# CAL_logics.net
KiCad netlist of a schematic drawn in Altium Designer
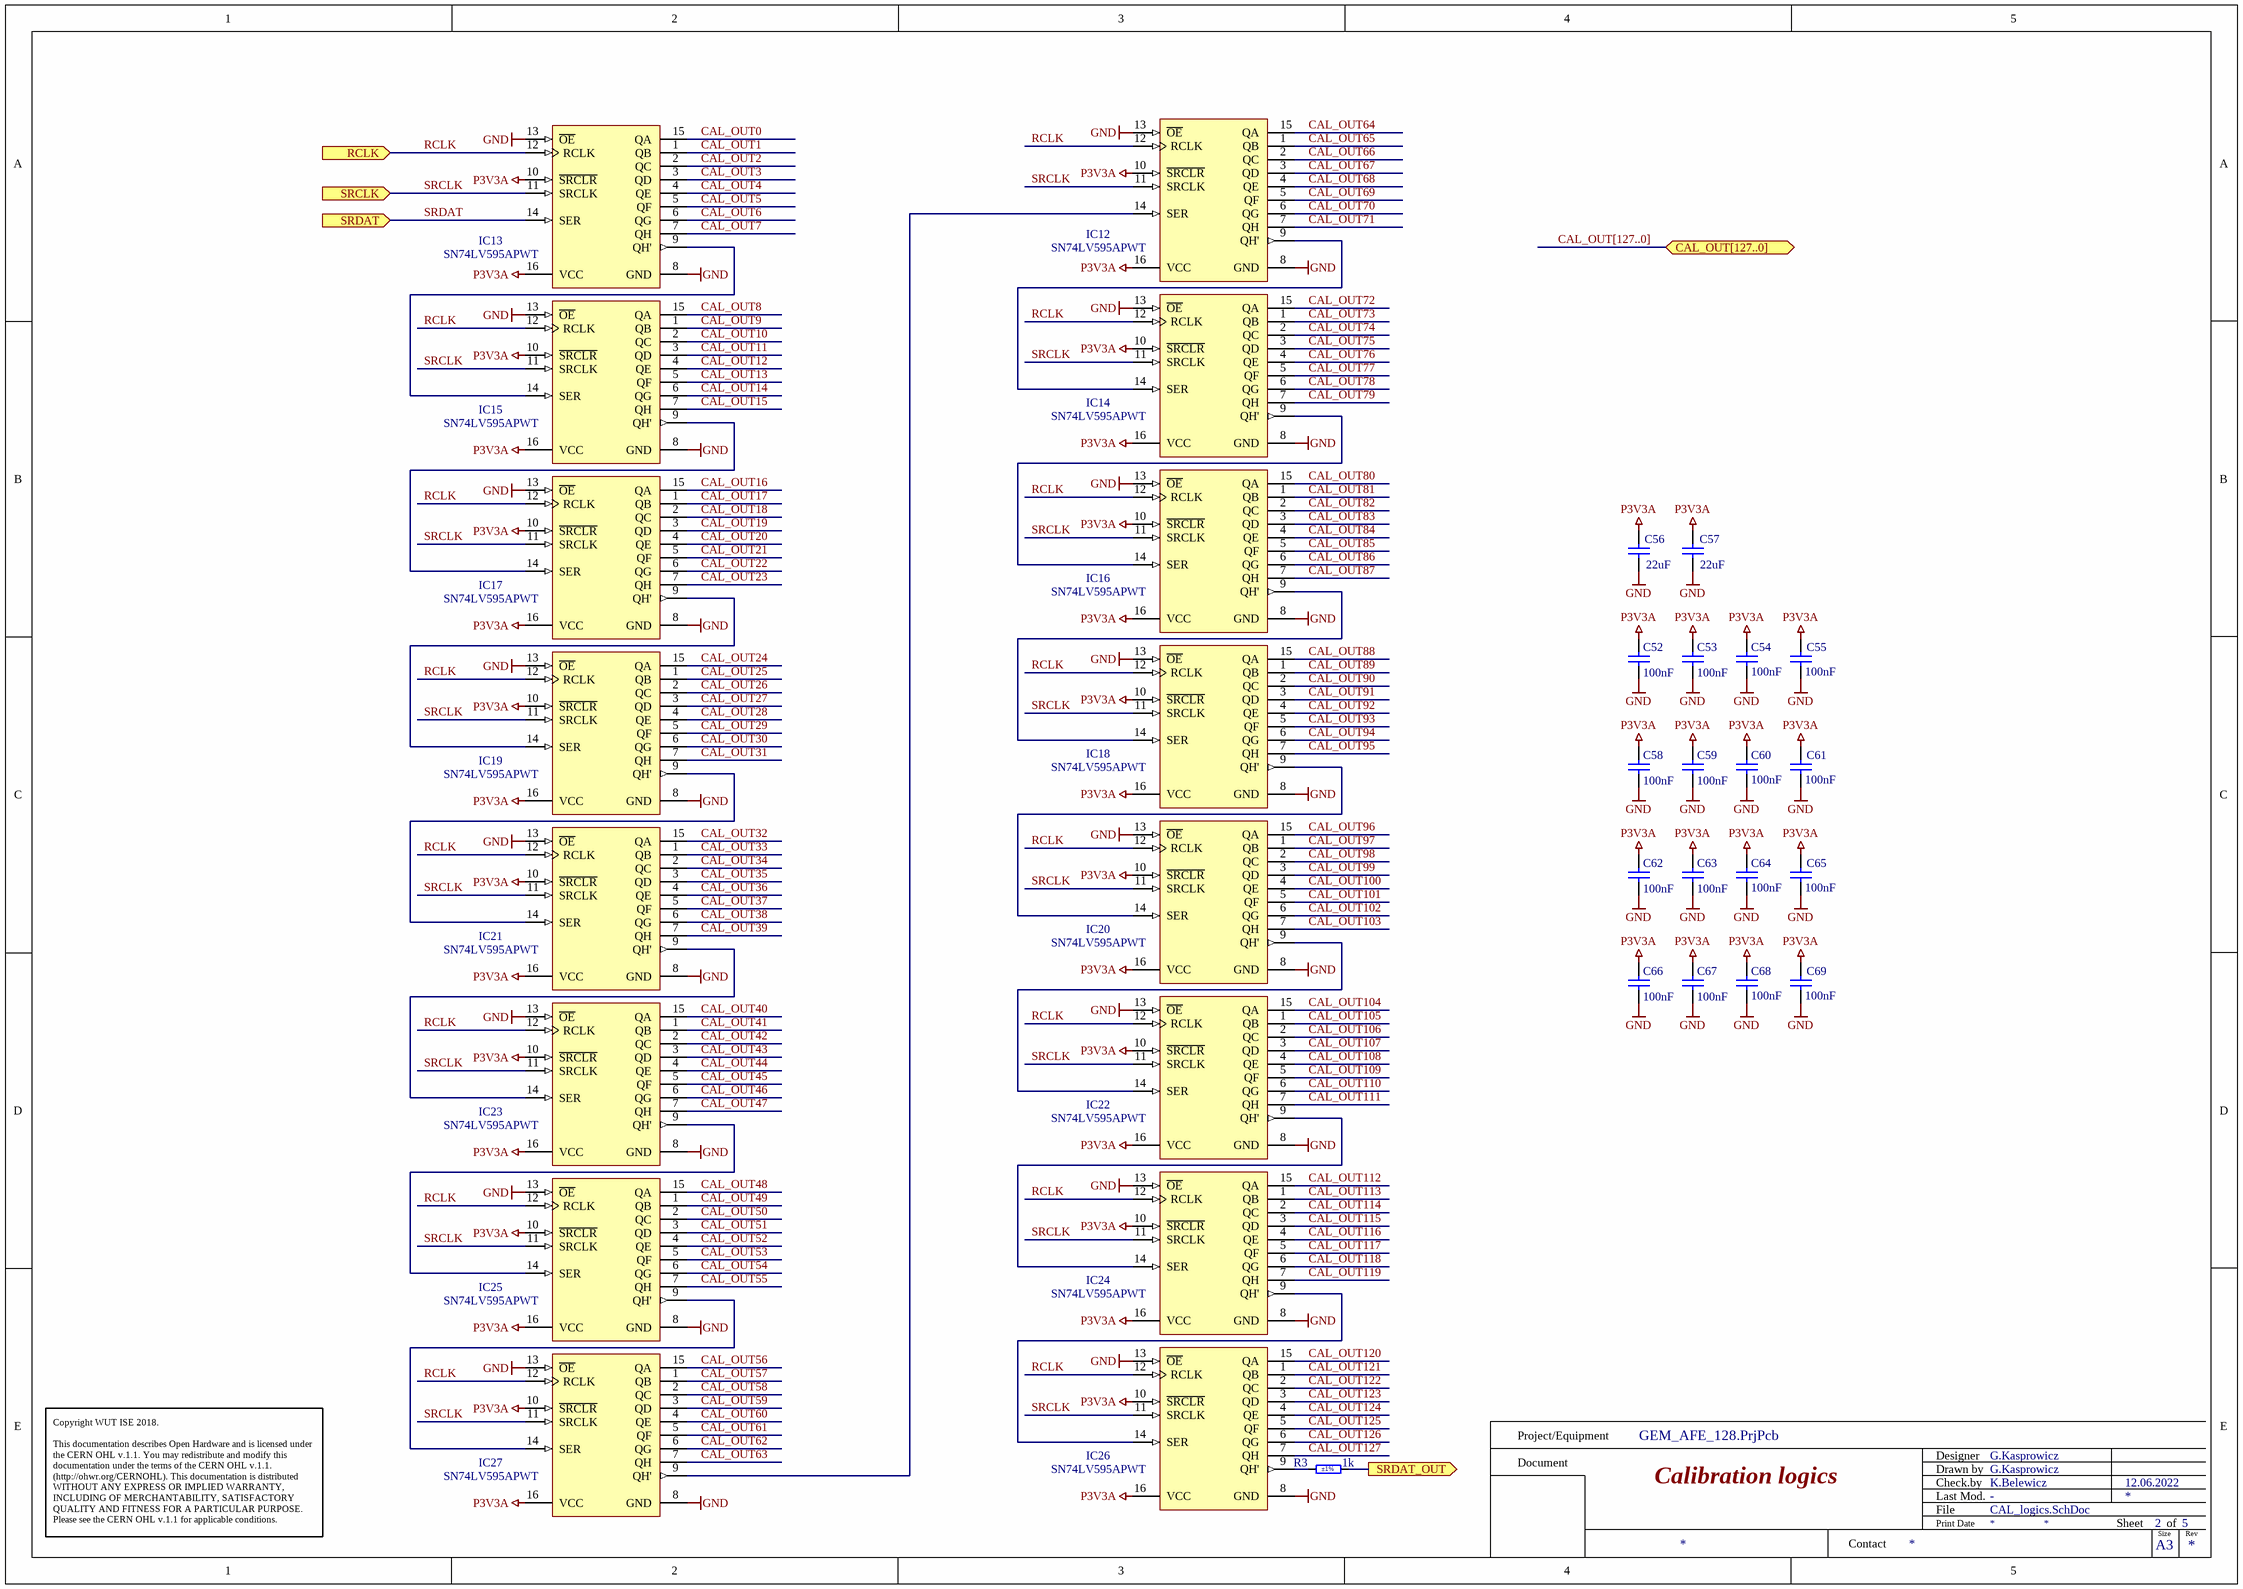
[diagram p0: CAL_logics.SchDoc]

(export (version "E")
  (design (tool "Eeschema 10.0.6"))
  (components
    (comp (ref "C52")
      (value "100nF")
      (footprint "CAPC1005X55N")
      (description "Non-polarised capacitor")
      (fields
        (field (name "PART NUMBER") "CC0402_100NF_16V_10%_X7R")
        (field (name "VOLTAGE") "16V")
        (field (name "AUTHOR") "CERN DEM JLC")
      )
      (libsource (lib "Capacitors") (part "Capacitor - non polarized"))
    )
    (comp (ref "C53")
      (value "100nF")
      (footprint "CAPC1005X55N")
      (description "Non-polarised capacitor")
      (fields
        (field (name "PART NUMBER") "CC0402_100NF_16V_10%_X7R")
        (field (name "VOLTAGE") "16V")
        (field (name "AUTHOR") "CERN DEM JLC")
      )
      (libsource (lib "Capacitors") (part "Capacitor - non polarized"))
    )
    (comp (ref "C54")
      (value "100nF")
      (footprint "CAPC1005X55N")
      (description "Non-polarised capacitor")
      (fields
        (field (name "PART NUMBER") "CC0402_100NF_16V_10%_X7R")
        (field (name "VOLTAGE") "16V")
        (field (name "AUTHOR") "CERN DEM JLC")
      )
      (libsource (lib "Capacitors") (part "Capacitor - non polarized"))
    )
    (comp (ref "C55")
      (value "100nF")
      (footprint "CAPC1005X55N")
      (description "Non-polarised capacitor")
      (fields
        (field (name "PART NUMBER") "CC0402_100NF_16V_10%_X7R")
        (field (name "VOLTAGE") "16V")
        (field (name "AUTHOR") "CERN DEM JLC")
      )
      (libsource (lib "Capacitors") (part "Capacitor - non polarized"))
    )
    (comp (ref "C56")
      (value "22uF")
      (footprint "CAPC3216X140N")
      (description "Non-polarised capacitor")
      (fields
        (field (name "PART NUMBER") "CC1206_22UF_6.3V_20%_X5R")
        (field (name "VOLTAGE") "6.3V")
        (field (name "AUTHOR") "CERN DEM JLC")
      )
      (libsource (lib "Capacitors") (part "Capacitor - non polarized"))
    )
    (comp (ref "C57")
      (value "22uF")
      (footprint "CAPC3216X140N")
      (description "Non-polarised capacitor")
      (fields
        (field (name "PART NUMBER") "CC1206_22UF_6.3V_20%_X5R")
        (field (name "VOLTAGE") "6.3V")
        (field (name "AUTHOR") "CERN DEM JLC")
      )
      (libsource (lib "Capacitors") (part "Capacitor - non polarized"))
    )
    (comp (ref "C58")
      (value "100nF")
      (footprint "CAPC1005X55N")
      (description "Non-polarised capacitor")
      (fields
        (field (name "PART NUMBER") "CC0402_100NF_16V_10%_X7R")
        (field (name "VOLTAGE") "16V")
        (field (name "AUTHOR") "CERN DEM JLC")
      )
      (libsource (lib "Capacitors") (part "Capacitor - non polarized"))
    )
    (comp (ref "C59")
      (value "100nF")
      (footprint "CAPC1005X55N")
      (description "Non-polarised capacitor")
      (fields
        (field (name "PART NUMBER") "CC0402_100NF_16V_10%_X7R")
        (field (name "VOLTAGE") "16V")
        (field (name "AUTHOR") "CERN DEM JLC")
      )
      (libsource (lib "Capacitors") (part "Capacitor - non polarized"))
    )
    (comp (ref "C60")
      (value "100nF")
      (footprint "CAPC1005X55N")
      (description "Non-polarised capacitor")
      (fields
        (field (name "PART NUMBER") "CC0402_100NF_16V_10%_X7R")
        (field (name "VOLTAGE") "16V")
        (field (name "AUTHOR") "CERN DEM JLC")
      )
      (libsource (lib "Capacitors") (part "Capacitor - non polarized"))
    )
    (comp (ref "C61")
      (value "100nF")
      (footprint "CAPC1005X55N")
      (description "Non-polarised capacitor")
      (fields
        (field (name "PART NUMBER") "CC0402_100NF_16V_10%_X7R")
        (field (name "VOLTAGE") "16V")
        (field (name "AUTHOR") "CERN DEM JLC")
      )
      (libsource (lib "Capacitors") (part "Capacitor - non polarized"))
    )
    (comp (ref "C62")
      (value "100nF")
      (footprint "CAPC1005X55N")
      (description "Non-polarised capacitor")
      (fields
        (field (name "PART NUMBER") "CC0402_100NF_16V_10%_X7R")
        (field (name "VOLTAGE") "16V")
        (field (name "AUTHOR") "CERN DEM JLC")
      )
      (libsource (lib "Capacitors") (part "Capacitor - non polarized"))
    )
    (comp (ref "C63")
      (value "100nF")
      (footprint "CAPC1005X55N")
      (description "Non-polarised capacitor")
      (fields
        (field (name "PART NUMBER") "CC0402_100NF_16V_10%_X7R")
        (field (name "VOLTAGE") "16V")
        (field (name "AUTHOR") "CERN DEM JLC")
      )
      (libsource (lib "Capacitors") (part "Capacitor - non polarized"))
    )
    (comp (ref "C64")
      (value "100nF")
      (footprint "CAPC1005X55N")
      (description "Non-polarised capacitor")
      (fields
        (field (name "PART NUMBER") "CC0402_100NF_16V_10%_X7R")
        (field (name "VOLTAGE") "16V")
        (field (name "AUTHOR") "CERN DEM JLC")
      )
      (libsource (lib "Capacitors") (part "Capacitor - non polarized"))
    )
    (comp (ref "C65")
      (value "100nF")
      (footprint "CAPC1005X55N")
      (description "Non-polarised capacitor")
      (fields
        (field (name "PART NUMBER") "CC0402_100NF_16V_10%_X7R")
        (field (name "VOLTAGE") "16V")
        (field (name "AUTHOR") "CERN DEM JLC")
      )
      (libsource (lib "Capacitors") (part "Capacitor - non polarized"))
    )
    (comp (ref "C66")
      (value "100nF")
      (footprint "CAPC1005X55N")
      (description "Non-polarised capacitor")
      (fields
        (field (name "PART NUMBER") "CC0402_100NF_16V_10%_X7R")
        (field (name "VOLTAGE") "16V")
        (field (name "AUTHOR") "CERN DEM JLC")
      )
      (libsource (lib "Capacitors") (part "Capacitor - non polarized"))
    )
    (comp (ref "C67")
      (value "100nF")
      (footprint "CAPC1005X55N")
      (description "Non-polarised capacitor")
      (fields
        (field (name "PART NUMBER") "CC0402_100NF_16V_10%_X7R")
        (field (name "VOLTAGE") "16V")
        (field (name "AUTHOR") "CERN DEM JLC")
      )
      (libsource (lib "Capacitors") (part "Capacitor - non polarized"))
    )
    (comp (ref "C68")
      (value "100nF")
      (footprint "CAPC1005X55N")
      (description "Non-polarised capacitor")
      (fields
        (field (name "PART NUMBER") "CC0402_100NF_16V_10%_X7R")
        (field (name "VOLTAGE") "16V")
        (field (name "AUTHOR") "CERN DEM JLC")
      )
      (libsource (lib "Capacitors") (part "Capacitor - non polarized"))
    )
    (comp (ref "C69")
      (value "100nF")
      (footprint "CAPC1005X55N")
      (description "Non-polarised capacitor")
      (fields
        (field (name "PART NUMBER") "CC0402_100NF_16V_10%_X7R")
        (field (name "VOLTAGE") "16V")
        (field (name "AUTHOR") "CERN DEM JLC")
      )
      (libsource (lib "Capacitors") (part "Capacitor - non polarized"))
    )
    (comp (ref "IC12")
      (value "SN74LV595APWT")
      (footprint "SOP65P640X120-16N")
      (description "8-Bit Shift Register With 3-State Output Register")
      (fields (field (name "MANUFACTURER") "TEXAS INSTRUMENTS") (field (name "AUTHOR") "CERN DEM JLC"))
      (libsource (lib "ICs And Semiconductors") (part "74595"))
    )
    (comp (ref "IC13")
      (value "SN74LV595APWT")
      (footprint "SOP65P640X120-16N")
      (description "8-Bit Shift Register With 3-State Output Register")
      (fields (field (name "MANUFACTURER") "TEXAS INSTRUMENTS") (field (name "AUTHOR") "CERN DEM JLC"))
      (libsource (lib "ICs And Semiconductors") (part "74595"))
    )
    (comp (ref "IC14")
      (value "SN74LV595APWT")
      (footprint "SOP65P640X120-16N")
      (description "8-Bit Shift Register With 3-State Output Register")
      (fields (field (name "MANUFACTURER") "TEXAS INSTRUMENTS") (field (name "AUTHOR") "CERN DEM JLC"))
      (libsource (lib "ICs And Semiconductors") (part "74595"))
    )
    (comp (ref "IC15")
      (value "SN74LV595APWT")
      (footprint "SOP65P640X120-16N")
      (description "8-Bit Shift Register With 3-State Output Register")
      (fields (field (name "MANUFACTURER") "TEXAS INSTRUMENTS") (field (name "AUTHOR") "CERN DEM JLC"))
      (libsource (lib "ICs And Semiconductors") (part "74595"))
    )
    (comp (ref "IC16")
      (value "SN74LV595APWT")
      (footprint "SOP65P640X120-16N")
      (description "8-Bit Shift Register With 3-State Output Register")
      (fields (field (name "MANUFACTURER") "TEXAS INSTRUMENTS") (field (name "AUTHOR") "CERN DEM JLC"))
      (libsource (lib "ICs And Semiconductors") (part "74595"))
    )
    (comp (ref "IC17")
      (value "SN74LV595APWT")
      (footprint "SOP65P640X120-16N")
      (description "8-Bit Shift Register With 3-State Output Register")
      (fields (field (name "MANUFACTURER") "TEXAS INSTRUMENTS") (field (name "AUTHOR") "CERN DEM JLC"))
      (libsource (lib "ICs And Semiconductors") (part "74595"))
    )
    (comp (ref "IC18")
      (value "SN74LV595APWT")
      (footprint "SOP65P640X120-16N")
      (description "8-Bit Shift Register With 3-State Output Register")
      (fields (field (name "MANUFACTURER") "TEXAS INSTRUMENTS") (field (name "AUTHOR") "CERN DEM JLC"))
      (libsource (lib "ICs And Semiconductors") (part "74595"))
    )
    (comp (ref "IC19")
      (value "SN74LV595APWT")
      (footprint "SOP65P640X120-16N")
      (description "8-Bit Shift Register With 3-State Output Register")
      (fields (field (name "MANUFACTURER") "TEXAS INSTRUMENTS") (field (name "AUTHOR") "CERN DEM JLC"))
      (libsource (lib "ICs And Semiconductors") (part "74595"))
    )
    (comp (ref "IC20")
      (value "SN74LV595APWT")
      (footprint "SOP65P640X120-16N")
      (description "8-Bit Shift Register With 3-State Output Register")
      (fields (field (name "MANUFACTURER") "TEXAS INSTRUMENTS") (field (name "AUTHOR") "CERN DEM JLC"))
      (libsource (lib "ICs And Semiconductors") (part "74595"))
    )
    (comp (ref "IC21")
      (value "SN74LV595APWT")
      (footprint "SOP65P640X120-16N")
      (description "8-Bit Shift Register With 3-State Output Register")
      (fields (field (name "MANUFACTURER") "TEXAS INSTRUMENTS") (field (name "AUTHOR") "CERN DEM JLC"))
      (libsource (lib "ICs And Semiconductors") (part "74595"))
    )
    (comp (ref "IC22")
      (value "SN74LV595APWT")
      (footprint "SOP65P640X120-16N")
      (description "8-Bit Shift Register With 3-State Output Register")
      (fields (field (name "MANUFACTURER") "TEXAS INSTRUMENTS") (field (name "AUTHOR") "CERN DEM JLC"))
      (libsource (lib "ICs And Semiconductors") (part "74595"))
    )
    (comp (ref "IC23")
      (value "SN74LV595APWT")
      (footprint "SOP65P640X120-16N")
      (description "8-Bit Shift Register With 3-State Output Register")
      (fields (field (name "MANUFACTURER") "TEXAS INSTRUMENTS") (field (name "AUTHOR") "CERN DEM JLC"))
      (libsource (lib "ICs And Semiconductors") (part "74595"))
    )
    (comp (ref "IC24")
      (value "SN74LV595APWT")
      (footprint "SOP65P640X120-16N")
      (description "8-Bit Shift Register With 3-State Output Register")
      (fields (field (name "MANUFACTURER") "TEXAS INSTRUMENTS") (field (name "AUTHOR") "CERN DEM JLC"))
      (libsource (lib "ICs And Semiconductors") (part "74595"))
    )
    (comp (ref "IC25")
      (value "SN74LV595APWT")
      (footprint "SOP65P640X120-16N")
      (description "8-Bit Shift Register With 3-State Output Register")
      (fields (field (name "MANUFACTURER") "TEXAS INSTRUMENTS") (field (name "AUTHOR") "CERN DEM JLC"))
      (libsource (lib "ICs And Semiconductors") (part "74595"))
    )
    (comp (ref "IC26")
      (value "SN74LV595APWT")
      (footprint "SOP65P640X120-16N")
      (description "8-Bit Shift Register With 3-State Output Register")
      (fields (field (name "MANUFACTURER") "TEXAS INSTRUMENTS") (field (name "AUTHOR") "CERN DEM JLC"))
      (libsource (lib "ICs And Semiconductors") (part "74595"))
    )
    (comp (ref "IC27")
      (value "SN74LV595APWT")
      (footprint "SOP65P640X120-16N")
      (description "8-Bit Shift Register With 3-State Output Register")
      (fields (field (name "MANUFACTURER") "TEXAS INSTRUMENTS") (field (name "AUTHOR") "CERN DEM JLC"))
      (libsource (lib "ICs And Semiconductors") (part "74595"))
    )
    (comp (ref "R3")
      (value "1k")
      (footprint "RESC1005X40N")
      (description "Resistor - 1%")
      (fields
        (field (name "TOLERANCE") "±1%")
        (field (name "PART NUMBER") "R0402_1K_1%_0.0625W_100PPM")
        (field (name "POWER") "0.0625W")
        (field (name "AUTHOR") "CERN DEM JLC")
      )
      (libsource (lib "Resistors") (part "Resistor - 1%"))
    )
  )
  (nets
    (net (code "1") (name "/CAL_OUT0") (class "Default")
      (node (ref "IC13") (pin "15") (pinfunction "QA_15") (pintype "tri_state"))
    )
    (net (code "2") (name "/CAL_OUT1") (class "Default")
      (node (ref "IC13") (pin "1") (pinfunction "QB_1") (pintype "tri_state"))
    )
    (net (code "3") (name "/CAL_OUT2") (class "Default")
      (node (ref "IC13") (pin "2") (pinfunction "QC_2") (pintype "tri_state"))
    )
    (net (code "4") (name "/CAL_OUT3") (class "Default")
      (node (ref "IC13") (pin "3") (pinfunction "QD_3") (pintype "tri_state"))
    )
    (net (code "5") (name "/CAL_OUT4") (class "Default")
      (node (ref "IC13") (pin "4") (pinfunction "QE_4") (pintype "tri_state"))
    )
    (net (code "6") (name "/CAL_OUT5") (class "Default")
      (node (ref "IC13") (pin "5") (pinfunction "QF_5") (pintype "tri_state"))
    )
    (net (code "7") (name "/CAL_OUT6") (class "Default")
      (node (ref "IC13") (pin "6") (pinfunction "QG_6") (pintype "tri_state"))
    )
    (net (code "8") (name "/CAL_OUT7") (class "Default")
      (node (ref "IC13") (pin "7") (pinfunction "QH_7") (pintype "tri_state"))
    )
    (net (code "9") (name "/CAL_OUT8") (class "Default")
      (node (ref "IC15") (pin "15") (pinfunction "QA_15") (pintype "tri_state"))
    )
    (net (code "10") (name "/CAL_OUT9") (class "Default")
      (node (ref "IC15") (pin "1") (pinfunction "QB_1") (pintype "tri_state"))
    )
    (net (code "11") (name "/CAL_OUT10") (class "Default")
      (node (ref "IC15") (pin "2") (pinfunction "QC_2") (pintype "tri_state"))
    )
    (net (code "12") (name "/CAL_OUT11") (class "Default")
      (node (ref "IC15") (pin "3") (pinfunction "QD_3") (pintype "tri_state"))
    )
    (net (code "13") (name "/CAL_OUT12") (class "Default")
      (node (ref "IC15") (pin "4") (pinfunction "QE_4") (pintype "tri_state"))
    )
    (net (code "14") (name "/CAL_OUT13") (class "Default")
      (node (ref "IC15") (pin "5") (pinfunction "QF_5") (pintype "tri_state"))
    )
    (net (code "15") (name "/CAL_OUT14") (class "Default")
      (node (ref "IC15") (pin "6") (pinfunction "QG_6") (pintype "tri_state"))
    )
    (net (code "16") (name "/CAL_OUT15") (class "Default")
      (node (ref "IC15") (pin "7") (pinfunction "QH_7") (pintype "tri_state"))
    )
    (net (code "17") (name "/CAL_OUT16") (class "Default")
      (node (ref "IC17") (pin "15") (pinfunction "QA_15") (pintype "tri_state"))
    )
    (net (code "18") (name "/CAL_OUT17") (class "Default")
      (node (ref "IC17") (pin "1") (pinfunction "QB_1") (pintype "tri_state"))
    )
    (net (code "19") (name "/CAL_OUT18") (class "Default")
      (node (ref "IC17") (pin "2") (pinfunction "QC_2") (pintype "tri_state"))
    )
    (net (code "20") (name "/CAL_OUT19") (class "Default")
      (node (ref "IC17") (pin "3") (pinfunction "QD_3") (pintype "tri_state"))
    )
    (net (code "21") (name "/CAL_OUT20") (class "Default")
      (node (ref "IC17") (pin "4") (pinfunction "QE_4") (pintype "tri_state"))
    )
    (net (code "22") (name "/CAL_OUT21") (class "Default")
      (node (ref "IC17") (pin "5") (pinfunction "QF_5") (pintype "tri_state"))
    )
    (net (code "23") (name "/CAL_OUT22") (class "Default")
      (node (ref "IC17") (pin "6") (pinfunction "QG_6") (pintype "tri_state"))
    )
    (net (code "24") (name "/CAL_OUT23") (class "Default")
      (node (ref "IC17") (pin "7") (pinfunction "QH_7") (pintype "tri_state"))
    )
    (net (code "25") (name "/CAL_OUT24") (class "Default")
      (node (ref "IC19") (pin "15") (pinfunction "QA_15") (pintype "tri_state"))
    )
    (net (code "26") (name "/CAL_OUT25") (class "Default")
      (node (ref "IC19") (pin "1") (pinfunction "QB_1") (pintype "tri_state"))
    )
    (net (code "27") (name "/CAL_OUT26") (class "Default")
      (node (ref "IC19") (pin "2") (pinfunction "QC_2") (pintype "tri_state"))
    )
    (net (code "28") (name "/CAL_OUT27") (class "Default")
      (node (ref "IC19") (pin "3") (pinfunction "QD_3") (pintype "tri_state"))
    )
    (net (code "29") (name "/CAL_OUT28") (class "Default")
      (node (ref "IC19") (pin "4") (pinfunction "QE_4") (pintype "tri_state"))
    )
    (net (code "30") (name "/CAL_OUT29") (class "Default")
      (node (ref "IC19") (pin "5") (pinfunction "QF_5") (pintype "tri_state"))
    )
    (net (code "31") (name "/CAL_OUT30") (class "Default")
      (node (ref "IC19") (pin "6") (pinfunction "QG_6") (pintype "tri_state"))
    )
    (net (code "32") (name "/CAL_OUT31") (class "Default")
      (node (ref "IC19") (pin "7") (pinfunction "QH_7") (pintype "tri_state"))
    )
    (net (code "33") (name "/CAL_OUT32") (class "Default")
      (node (ref "IC21") (pin "15") (pinfunction "QA_15") (pintype "tri_state"))
    )
    (net (code "34") (name "/CAL_OUT33") (class "Default")
      (node (ref "IC21") (pin "1") (pinfunction "QB_1") (pintype "tri_state"))
    )
    (net (code "35") (name "/CAL_OUT34") (class "Default")
      (node (ref "IC21") (pin "2") (pinfunction "QC_2") (pintype "tri_state"))
    )
    (net (code "36") (name "/CAL_OUT35") (class "Default")
      (node (ref "IC21") (pin "3") (pinfunction "QD_3") (pintype "tri_state"))
    )
    (net (code "37") (name "/CAL_OUT36") (class "Default")
      (node (ref "IC21") (pin "4") (pinfunction "QE_4") (pintype "tri_state"))
    )
    (net (code "38") (name "/CAL_OUT37") (class "Default")
      (node (ref "IC21") (pin "5") (pinfunction "QF_5") (pintype "tri_state"))
    )
    (net (code "39") (name "/CAL_OUT38") (class "Default")
      (node (ref "IC21") (pin "6") (pinfunction "QG_6") (pintype "tri_state"))
    )
    (net (code "40") (name "/CAL_OUT39") (class "Default")
      (node (ref "IC21") (pin "7") (pinfunction "QH_7") (pintype "tri_state"))
    )
    (net (code "41") (name "/CAL_OUT40") (class "Default")
      (node (ref "IC23") (pin "15") (pinfunction "QA_15") (pintype "tri_state"))
    )
    (net (code "42") (name "/CAL_OUT41") (class "Default")
      (node (ref "IC23") (pin "1") (pinfunction "QB_1") (pintype "tri_state"))
    )
    (net (code "43") (name "/CAL_OUT42") (class "Default")
      (node (ref "IC23") (pin "2") (pinfunction "QC_2") (pintype "tri_state"))
    )
    (net (code "44") (name "/CAL_OUT43") (class "Default")
      (node (ref "IC23") (pin "3") (pinfunction "QD_3") (pintype "tri_state"))
    )
    (net (code "45") (name "/CAL_OUT44") (class "Default")
      (node (ref "IC23") (pin "4") (pinfunction "QE_4") (pintype "tri_state"))
    )
    (net (code "46") (name "/CAL_OUT45") (class "Default")
      (node (ref "IC23") (pin "5") (pinfunction "QF_5") (pintype "tri_state"))
    )
    (net (code "47") (name "/CAL_OUT46") (class "Default")
      (node (ref "IC23") (pin "6") (pinfunction "QG_6") (pintype "tri_state"))
    )
    (net (code "48") (name "/CAL_OUT47") (class "Default")
      (node (ref "IC23") (pin "7") (pinfunction "QH_7") (pintype "tri_state"))
    )
    (net (code "49") (name "/CAL_OUT48") (class "Default")
      (node (ref "IC25") (pin "15") (pinfunction "QA_15") (pintype "tri_state"))
    )
    (net (code "50") (name "/CAL_OUT49") (class "Default")
      (node (ref "IC25") (pin "1") (pinfunction "QB_1") (pintype "tri_state"))
    )
    (net (code "51") (name "/CAL_OUT50") (class "Default")
      (node (ref "IC25") (pin "2") (pinfunction "QC_2") (pintype "tri_state"))
    )
    (net (code "52") (name "/CAL_OUT51") (class "Default")
      (node (ref "IC25") (pin "3") (pinfunction "QD_3") (pintype "tri_state"))
    )
    (net (code "53") (name "/CAL_OUT52") (class "Default")
      (node (ref "IC25") (pin "4") (pinfunction "QE_4") (pintype "tri_state"))
    )
    (net (code "54") (name "/CAL_OUT53") (class "Default")
      (node (ref "IC25") (pin "5") (pinfunction "QF_5") (pintype "tri_state"))
    )
    (net (code "55") (name "/CAL_OUT54") (class "Default")
      (node (ref "IC25") (pin "6") (pinfunction "QG_6") (pintype "tri_state"))
    )
    (net (code "56") (name "/CAL_OUT55") (class "Default")
      (node (ref "IC25") (pin "7") (pinfunction "QH_7") (pintype "tri_state"))
    )
    (net (code "57") (name "/CAL_OUT56") (class "Default")
      (node (ref "IC27") (pin "15") (pinfunction "QA_15") (pintype "tri_state"))
    )
    (net (code "58") (name "/CAL_OUT57") (class "Default")
      (node (ref "IC27") (pin "1") (pinfunction "QB_1") (pintype "tri_state"))
    )
    (net (code "59") (name "/CAL_OUT58") (class "Default")
      (node (ref "IC27") (pin "2") (pinfunction "QC_2") (pintype "tri_state"))
    )
    (net (code "60") (name "/CAL_OUT59") (class "Default")
      (node (ref "IC27") (pin "3") (pinfunction "QD_3") (pintype "tri_state"))
    )
    (net (code "61") (name "/CAL_OUT60") (class "Default")
      (node (ref "IC27") (pin "4") (pinfunction "QE_4") (pintype "tri_state"))
    )
    (net (code "62") (name "/CAL_OUT61") (class "Default")
      (node (ref "IC27") (pin "5") (pinfunction "QF_5") (pintype "tri_state"))
    )
    (net (code "63") (name "/CAL_OUT62") (class "Default")
      (node (ref "IC27") (pin "6") (pinfunction "QG_6") (pintype "tri_state"))
    )
    (net (code "64") (name "/CAL_OUT63") (class "Default")
      (node (ref "IC27") (pin "7") (pinfunction "QH_7") (pintype "tri_state"))
    )
    (net (code "65") (name "/CAL_OUT64") (class "Default")
      (node (ref "IC12") (pin "15") (pinfunction "QA_15") (pintype "tri_state"))
    )
    (net (code "66") (name "/CAL_OUT65") (class "Default")
      (node (ref "IC12") (pin "1") (pinfunction "QB_1") (pintype "tri_state"))
    )
    (net (code "67") (name "/CAL_OUT66") (class "Default")
      (node (ref "IC12") (pin "2") (pinfunction "QC_2") (pintype "tri_state"))
    )
    (net (code "68") (name "/CAL_OUT67") (class "Default")
      (node (ref "IC12") (pin "3") (pinfunction "QD_3") (pintype "tri_state"))
    )
    (net (code "69") (name "/CAL_OUT68") (class "Default")
      (node (ref "IC12") (pin "4") (pinfunction "QE_4") (pintype "tri_state"))
    )
    (net (code "70") (name "/CAL_OUT69") (class "Default")
      (node (ref "IC12") (pin "5") (pinfunction "QF_5") (pintype "tri_state"))
    )
    (net (code "71") (name "/CAL_OUT70") (class "Default")
      (node (ref "IC12") (pin "6") (pinfunction "QG_6") (pintype "tri_state"))
    )
    (net (code "72") (name "/CAL_OUT71") (class "Default")
      (node (ref "IC12") (pin "7") (pinfunction "QH_7") (pintype "tri_state"))
    )
    (net (code "73") (name "/CAL_OUT72") (class "Default")
      (node (ref "IC14") (pin "15") (pinfunction "QA_15") (pintype "tri_state"))
    )
    (net (code "74") (name "/CAL_OUT73") (class "Default")
      (node (ref "IC14") (pin "1") (pinfunction "QB_1") (pintype "tri_state"))
    )
    (net (code "75") (name "/CAL_OUT74") (class "Default")
      (node (ref "IC14") (pin "2") (pinfunction "QC_2") (pintype "tri_state"))
    )
    (net (code "76") (name "/CAL_OUT75") (class "Default")
      (node (ref "IC14") (pin "3") (pinfunction "QD_3") (pintype "tri_state"))
    )
    (net (code "77") (name "/CAL_OUT76") (class "Default")
      (node (ref "IC14") (pin "4") (pinfunction "QE_4") (pintype "tri_state"))
    )
    (net (code "78") (name "/CAL_OUT77") (class "Default")
      (node (ref "IC14") (pin "5") (pinfunction "QF_5") (pintype "tri_state"))
    )
    (net (code "79") (name "/CAL_OUT78") (class "Default")
      (node (ref "IC14") (pin "6") (pinfunction "QG_6") (pintype "tri_state"))
    )
    (net (code "80") (name "/CAL_OUT79") (class "Default")
      (node (ref "IC14") (pin "7") (pinfunction "QH_7") (pintype "tri_state"))
    )
    (net (code "81") (name "/CAL_OUT80") (class "Default")
      (node (ref "IC16") (pin "15") (pinfunction "QA_15") (pintype "tri_state"))
    )
    (net (code "82") (name "/CAL_OUT81") (class "Default")
      (node (ref "IC16") (pin "1") (pinfunction "QB_1") (pintype "tri_state"))
    )
    (net (code "83") (name "/CAL_OUT82") (class "Default")
      (node (ref "IC16") (pin "2") (pinfunction "QC_2") (pintype "tri_state"))
    )
    (net (code "84") (name "/CAL_OUT83") (class "Default")
      (node (ref "IC16") (pin "3") (pinfunction "QD_3") (pintype "tri_state"))
    )
    (net (code "85") (name "/CAL_OUT84") (class "Default")
      (node (ref "IC16") (pin "4") (pinfunction "QE_4") (pintype "tri_state"))
    )
    (net (code "86") (name "/CAL_OUT85") (class "Default")
      (node (ref "IC16") (pin "5") (pinfunction "QF_5") (pintype "tri_state"))
    )
    (net (code "87") (name "/CAL_OUT86") (class "Default")
      (node (ref "IC16") (pin "6") (pinfunction "QG_6") (pintype "tri_state"))
    )
    (net (code "88") (name "/CAL_OUT87") (class "Default")
      (node (ref "IC16") (pin "7") (pinfunction "QH_7") (pintype "tri_state"))
    )
    (net (code "89") (name "/CAL_OUT88") (class "Default")
      (node (ref "IC18") (pin "15") (pinfunction "QA_15") (pintype "tri_state"))
    )
    (net (code "90") (name "/CAL_OUT89") (class "Default")
      (node (ref "IC18") (pin "1") (pinfunction "QB_1") (pintype "tri_state"))
    )
    (net (code "91") (name "/CAL_OUT90") (class "Default")
      (node (ref "IC18") (pin "2") (pinfunction "QC_2") (pintype "tri_state"))
    )
    (net (code "92") (name "/CAL_OUT91") (class "Default")
      (node (ref "IC18") (pin "3") (pinfunction "QD_3") (pintype "tri_state"))
    )
    (net (code "93") (name "/CAL_OUT92") (class "Default")
      (node (ref "IC18") (pin "4") (pinfunction "QE_4") (pintype "tri_state"))
    )
    (net (code "94") (name "/CAL_OUT93") (class "Default")
      (node (ref "IC18") (pin "5") (pinfunction "QF_5") (pintype "tri_state"))
    )
    (net (code "95") (name "/CAL_OUT94") (class "Default")
      (node (ref "IC18") (pin "6") (pinfunction "QG_6") (pintype "tri_state"))
    )
    (net (code "96") (name "/CAL_OUT95") (class "Default")
      (node (ref "IC18") (pin "7") (pinfunction "QH_7") (pintype "tri_state"))
    )
    (net (code "97") (name "/CAL_OUT96") (class "Default")
      (node (ref "IC20") (pin "15") (pinfunction "QA_15") (pintype "tri_state"))
    )
    (net (code "98") (name "/CAL_OUT97") (class "Default")
      (node (ref "IC20") (pin "1") (pinfunction "QB_1") (pintype "tri_state"))
    )
    (net (code "99") (name "/CAL_OUT98") (class "Default")
      (node (ref "IC20") (pin "2") (pinfunction "QC_2") (pintype "tri_state"))
    )
    (net (code "100") (name "/CAL_OUT99") (class "Default")
      (node (ref "IC20") (pin "3") (pinfunction "QD_3") (pintype "tri_state"))
    )
    (net (code "101") (name "/CAL_OUT100") (class "Default")
      (node (ref "IC20") (pin "4") (pinfunction "QE_4") (pintype "tri_state"))
    )
    (net (code "102") (name "/CAL_OUT101") (class "Default")
      (node (ref "IC20") (pin "5") (pinfunction "QF_5") (pintype "tri_state"))
    )
    (net (code "103") (name "/CAL_OUT102") (class "Default")
      (node (ref "IC20") (pin "6") (pinfunction "QG_6") (pintype "tri_state"))
    )
    (net (code "104") (name "/CAL_OUT103") (class "Default")
      (node (ref "IC20") (pin "7") (pinfunction "QH_7") (pintype "tri_state"))
    )
    (net (code "105") (name "/CAL_OUT104") (class "Default")
      (node (ref "IC22") (pin "15") (pinfunction "QA_15") (pintype "tri_state"))
    )
    (net (code "106") (name "/CAL_OUT105") (class "Default")
      (node (ref "IC22") (pin "1") (pinfunction "QB_1") (pintype "tri_state"))
    )
    (net (code "107") (name "/CAL_OUT106") (class "Default")
      (node (ref "IC22") (pin "2") (pinfunction "QC_2") (pintype "tri_state"))
    )
    (net (code "108") (name "/CAL_OUT107") (class "Default")
      (node (ref "IC22") (pin "3") (pinfunction "QD_3") (pintype "tri_state"))
    )
    (net (code "109") (name "/CAL_OUT108") (class "Default")
      (node (ref "IC22") (pin "4") (pinfunction "QE_4") (pintype "tri_state"))
    )
    (net (code "110") (name "/CAL_OUT109") (class "Default")
      (node (ref "IC22") (pin "5") (pinfunction "QF_5") (pintype "tri_state"))
    )
    (net (code "111") (name "/CAL_OUT110") (class "Default")
      (node (ref "IC22") (pin "6") (pinfunction "QG_6") (pintype "tri_state"))
    )
    (net (code "112") (name "/CAL_OUT111") (class "Default")
      (node (ref "IC22") (pin "7") (pinfunction "QH_7") (pintype "tri_state"))
    )
    (net (code "113") (name "/CAL_OUT112") (class "Default")
      (node (ref "IC24") (pin "15") (pinfunction "QA_15") (pintype "tri_state"))
    )
    (net (code "114") (name "/CAL_OUT113") (class "Default")
      (node (ref "IC24") (pin "1") (pinfunction "QB_1") (pintype "tri_state"))
    )
    (net (code "115") (name "/CAL_OUT114") (class "Default")
      (node (ref "IC24") (pin "2") (pinfunction "QC_2") (pintype "tri_state"))
    )
    (net (code "116") (name "/CAL_OUT115") (class "Default")
      (node (ref "IC24") (pin "3") (pinfunction "QD_3") (pintype "tri_state"))
    )
    (net (code "117") (name "/CAL_OUT116") (class "Default")
      (node (ref "IC24") (pin "4") (pinfunction "QE_4") (pintype "tri_state"))
    )
    (net (code "118") (name "/CAL_OUT117") (class "Default")
      (node (ref "IC24") (pin "5") (pinfunction "QF_5") (pintype "tri_state"))
    )
    (net (code "119") (name "/CAL_OUT118") (class "Default")
      (node (ref "IC24") (pin "6") (pinfunction "QG_6") (pintype "tri_state"))
    )
    (net (code "120") (name "/CAL_OUT119") (class "Default")
      (node (ref "IC24") (pin "7") (pinfunction "QH_7") (pintype "tri_state"))
    )
    (net (code "121") (name "/CAL_OUT120") (class "Default")
      (node (ref "IC26") (pin "15") (pinfunction "QA_15") (pintype "tri_state"))
    )
    (net (code "122") (name "/CAL_OUT121") (class "Default")
      (node (ref "IC26") (pin "1") (pinfunction "QB_1") (pintype "tri_state"))
    )
    (net (code "123") (name "/CAL_OUT122") (class "Default")
      (node (ref "IC26") (pin "2") (pinfunction "QC_2") (pintype "tri_state"))
    )
    (net (code "124") (name "/CAL_OUT123") (class "Default")
      (node (ref "IC26") (pin "3") (pinfunction "QD_3") (pintype "tri_state"))
    )
    (net (code "125") (name "/CAL_OUT124") (class "Default")
      (node (ref "IC26") (pin "4") (pinfunction "QE_4") (pintype "tri_state"))
    )
    (net (code "126") (name "/CAL_OUT125") (class "Default")
      (node (ref "IC26") (pin "5") (pinfunction "QF_5") (pintype "tri_state"))
    )
    (net (code "127") (name "/CAL_OUT126") (class "Default")
      (node (ref "IC26") (pin "6") (pinfunction "QG_6") (pintype "tri_state"))
    )
    (net (code "128") (name "/CAL_OUT127") (class "Default")
      (node (ref "IC26") (pin "7") (pinfunction "QH_7") (pintype "tri_state"))
    )
    (net (code "130") (name "/RCLK") (class "Default")
      (node (ref "IC12") (pin "12") (pinfunction "RCLK_12") (pintype "input"))
      (node (ref "IC13") (pin "12") (pinfunction "RCLK_12") (pintype "input"))
      (node (ref "IC14") (pin "12") (pinfunction "RCLK_12") (pintype "input"))
      (node (ref "IC15") (pin "12") (pinfunction "RCLK_12") (pintype "input"))
      (node (ref "IC16") (pin "12") (pinfunction "RCLK_12") (pintype "input"))
      (node (ref "IC17") (pin "12") (pinfunction "RCLK_12") (pintype "input"))
      (node (ref "IC18") (pin "12") (pinfunction "RCLK_12") (pintype "input"))
      (node (ref "IC19") (pin "12") (pinfunction "RCLK_12") (pintype "input"))
      (node (ref "IC20") (pin "12") (pinfunction "RCLK_12") (pintype "input"))
      (node (ref "IC21") (pin "12") (pinfunction "RCLK_12") (pintype "input"))
      (node (ref "IC22") (pin "12") (pinfunction "RCLK_12") (pintype "input"))
      (node (ref "IC23") (pin "12") (pinfunction "RCLK_12") (pintype "input"))
      (node (ref "IC24") (pin "12") (pinfunction "RCLK_12") (pintype "input"))
      (node (ref "IC25") (pin "12") (pinfunction "RCLK_12") (pintype "input"))
      (node (ref "IC26") (pin "12") (pinfunction "RCLK_12") (pintype "input"))
      (node (ref "IC27") (pin "12") (pinfunction "RCLK_12") (pintype "input"))
    )
    (net (code "131") (name "/SRCLK") (class "Default")
      (node (ref "IC12") (pin "11") (pinfunction "SRCLK_11") (pintype "input"))
      (node (ref "IC13") (pin "11") (pinfunction "SRCLK_11") (pintype "input"))
      (node (ref "IC14") (pin "11") (pinfunction "SRCLK_11") (pintype "input"))
      (node (ref "IC15") (pin "11") (pinfunction "SRCLK_11") (pintype "input"))
      (node (ref "IC16") (pin "11") (pinfunction "SRCLK_11") (pintype "input"))
      (node (ref "IC17") (pin "11") (pinfunction "SRCLK_11") (pintype "input"))
      (node (ref "IC18") (pin "11") (pinfunction "SRCLK_11") (pintype "input"))
      (node (ref "IC19") (pin "11") (pinfunction "SRCLK_11") (pintype "input"))
      (node (ref "IC20") (pin "11") (pinfunction "SRCLK_11") (pintype "input"))
      (node (ref "IC21") (pin "11") (pinfunction "SRCLK_11") (pintype "input"))
      (node (ref "IC22") (pin "11") (pinfunction "SRCLK_11") (pintype "input"))
      (node (ref "IC23") (pin "11") (pinfunction "SRCLK_11") (pintype "input"))
      (node (ref "IC24") (pin "11") (pinfunction "SRCLK_11") (pintype "input"))
      (node (ref "IC25") (pin "11") (pinfunction "SRCLK_11") (pintype "input"))
      (node (ref "IC26") (pin "11") (pinfunction "SRCLK_11") (pintype "input"))
      (node (ref "IC27") (pin "11") (pinfunction "SRCLK_11") (pintype "input"))
    )
    (net (code "132") (name "/SRDAT") (class "Default")
      (node (ref "IC13") (pin "14") (pinfunction "SER_14") (pintype "input"))
    )
    (net (code "133") (name "/SRDAT_OUT") (class "Default")
      (node (ref "R3") (pin "2") (pinfunction "2_2") (pintype "passive"))
    )
    (net (code "134") (name "GND") (class "Default")
      (node (ref "C52") (pin "1") (pinfunction "1_1") (pintype "passive"))
      (node (ref "C53") (pin "1") (pinfunction "1_1") (pintype "passive"))
      (node (ref "C54") (pin "1") (pinfunction "1_1") (pintype "passive"))
      (node (ref "C55") (pin "1") (pinfunction "1_1") (pintype "passive"))
      (node (ref "C56") (pin "1") (pinfunction "1_1") (pintype "passive"))
      (node (ref "C57") (pin "1") (pinfunction "1_1") (pintype "passive"))
      (node (ref "C58") (pin "1") (pinfunction "1_1") (pintype "passive"))
      (node (ref "C59") (pin "1") (pinfunction "1_1") (pintype "passive"))
      (node (ref "C60") (pin "1") (pinfunction "1_1") (pintype "passive"))
      (node (ref "C61") (pin "1") (pinfunction "1_1") (pintype "passive"))
      (node (ref "C62") (pin "1") (pinfunction "1_1") (pintype "passive"))
      (node (ref "C63") (pin "1") (pinfunction "1_1") (pintype "passive"))
      (node (ref "C64") (pin "1") (pinfunction "1_1") (pintype "passive"))
      (node (ref "C65") (pin "1") (pinfunction "1_1") (pintype "passive"))
      (node (ref "C66") (pin "1") (pinfunction "1_1") (pintype "passive"))
      (node (ref "C67") (pin "1") (pinfunction "1_1") (pintype "passive"))
      (node (ref "C68") (pin "1") (pinfunction "1_1") (pintype "passive"))
      (node (ref "C69") (pin "1") (pinfunction "1_1") (pintype "passive"))
      (node (ref "IC12") (pin "13") (pinfunction "~{OE}_13") (pintype "input"))
      (node (ref "IC12") (pin "8") (pinfunction "GND_8") (pintype "power_in"))
      (node (ref "IC13") (pin "13") (pinfunction "~{OE}_13") (pintype "input"))
      (node (ref "IC13") (pin "8") (pinfunction "GND_8") (pintype "power_in"))
      (node (ref "IC14") (pin "13") (pinfunction "~{OE}_13") (pintype "input"))
      (node (ref "IC14") (pin "8") (pinfunction "GND_8") (pintype "power_in"))
      (node (ref "IC15") (pin "13") (pinfunction "~{OE}_13") (pintype "input"))
      (node (ref "IC15") (pin "8") (pinfunction "GND_8") (pintype "power_in"))
      (node (ref "IC16") (pin "13") (pinfunction "~{OE}_13") (pintype "input"))
      (node (ref "IC16") (pin "8") (pinfunction "GND_8") (pintype "power_in"))
      (node (ref "IC17") (pin "13") (pinfunction "~{OE}_13") (pintype "input"))
      (node (ref "IC17") (pin "8") (pinfunction "GND_8") (pintype "power_in"))
      (node (ref "IC18") (pin "13") (pinfunction "~{OE}_13") (pintype "input"))
      (node (ref "IC18") (pin "8") (pinfunction "GND_8") (pintype "power_in"))
      (node (ref "IC19") (pin "13") (pinfunction "~{OE}_13") (pintype "input"))
      (node (ref "IC19") (pin "8") (pinfunction "GND_8") (pintype "power_in"))
      (node (ref "IC20") (pin "13") (pinfunction "~{OE}_13") (pintype "input"))
      (node (ref "IC20") (pin "8") (pinfunction "GND_8") (pintype "power_in"))
      (node (ref "IC21") (pin "13") (pinfunction "~{OE}_13") (pintype "input"))
      (node (ref "IC21") (pin "8") (pinfunction "GND_8") (pintype "power_in"))
      (node (ref "IC22") (pin "13") (pinfunction "~{OE}_13") (pintype "input"))
      (node (ref "IC22") (pin "8") (pinfunction "GND_8") (pintype "power_in"))
      (node (ref "IC23") (pin "13") (pinfunction "~{OE}_13") (pintype "input"))
      (node (ref "IC23") (pin "8") (pinfunction "GND_8") (pintype "power_in"))
      (node (ref "IC24") (pin "13") (pinfunction "~{OE}_13") (pintype "input"))
      (node (ref "IC24") (pin "8") (pinfunction "GND_8") (pintype "power_in"))
      (node (ref "IC25") (pin "13") (pinfunction "~{OE}_13") (pintype "input"))
      (node (ref "IC25") (pin "8") (pinfunction "GND_8") (pintype "power_in"))
      (node (ref "IC26") (pin "13") (pinfunction "~{OE}_13") (pintype "input"))
      (node (ref "IC26") (pin "8") (pinfunction "GND_8") (pintype "power_in"))
      (node (ref "IC27") (pin "13") (pinfunction "~{OE}_13") (pintype "input"))
      (node (ref "IC27") (pin "8") (pinfunction "GND_8") (pintype "power_in"))
    )
    (net (code "135") (name "Net-(IC12-QH')") (class "Default")
      (node (ref "IC12") (pin "9") (pinfunction "QH'_9") (pintype "output"))
      (node (ref "IC14") (pin "14") (pinfunction "SER_14") (pintype "input"))
    )
    (net (code "136") (name "Net-(IC12-SER)") (class "Default")
      (node (ref "IC12") (pin "14") (pinfunction "SER_14") (pintype "input"))
      (node (ref "IC27") (pin "9") (pinfunction "QH'_9") (pintype "output"))
    )
    (net (code "137") (name "Net-(IC13-QH')") (class "Default")
      (node (ref "IC13") (pin "9") (pinfunction "QH'_9") (pintype "output"))
      (node (ref "IC15") (pin "14") (pinfunction "SER_14") (pintype "input"))
    )
    (net (code "138") (name "Net-(IC14-QH')") (class "Default")
      (node (ref "IC14") (pin "9") (pinfunction "QH'_9") (pintype "output"))
      (node (ref "IC16") (pin "14") (pinfunction "SER_14") (pintype "input"))
    )
    (net (code "139") (name "Net-(IC15-QH')") (class "Default")
      (node (ref "IC15") (pin "9") (pinfunction "QH'_9") (pintype "output"))
      (node (ref "IC17") (pin "14") (pinfunction "SER_14") (pintype "input"))
    )
    (net (code "140") (name "Net-(IC16-QH')") (class "Default")
      (node (ref "IC16") (pin "9") (pinfunction "QH'_9") (pintype "output"))
      (node (ref "IC18") (pin "14") (pinfunction "SER_14") (pintype "input"))
    )
    (net (code "141") (name "Net-(IC17-QH')") (class "Default")
      (node (ref "IC17") (pin "9") (pinfunction "QH'_9") (pintype "output"))
      (node (ref "IC19") (pin "14") (pinfunction "SER_14") (pintype "input"))
    )
    (net (code "142") (name "Net-(IC18-QH')") (class "Default")
      (node (ref "IC18") (pin "9") (pinfunction "QH'_9") (pintype "output"))
      (node (ref "IC20") (pin "14") (pinfunction "SER_14") (pintype "input"))
    )
    (net (code "143") (name "Net-(IC19-QH')") (class "Default")
      (node (ref "IC19") (pin "9") (pinfunction "QH'_9") (pintype "output"))
      (node (ref "IC21") (pin "14") (pinfunction "SER_14") (pintype "input"))
    )
    (net (code "144") (name "Net-(IC20-QH')") (class "Default")
      (node (ref "IC20") (pin "9") (pinfunction "QH'_9") (pintype "output"))
      (node (ref "IC22") (pin "14") (pinfunction "SER_14") (pintype "input"))
    )
    (net (code "145") (name "Net-(IC21-QH')") (class "Default")
      (node (ref "IC21") (pin "9") (pinfunction "QH'_9") (pintype "output"))
      (node (ref "IC23") (pin "14") (pinfunction "SER_14") (pintype "input"))
    )
    (net (code "146") (name "Net-(IC22-QH')") (class "Default")
      (node (ref "IC22") (pin "9") (pinfunction "QH'_9") (pintype "output"))
      (node (ref "IC24") (pin "14") (pinfunction "SER_14") (pintype "input"))
    )
    (net (code "147") (name "Net-(IC23-QH')") (class "Default")
      (node (ref "IC23") (pin "9") (pinfunction "QH'_9") (pintype "output"))
      (node (ref "IC25") (pin "14") (pinfunction "SER_14") (pintype "input"))
    )
    (net (code "148") (name "Net-(IC24-QH')") (class "Default")
      (node (ref "IC24") (pin "9") (pinfunction "QH'_9") (pintype "output"))
      (node (ref "IC26") (pin "14") (pinfunction "SER_14") (pintype "input"))
    )
    (net (code "149") (name "Net-(IC25-QH')") (class "Default")
      (node (ref "IC25") (pin "9") (pinfunction "QH'_9") (pintype "output"))
      (node (ref "IC27") (pin "14") (pinfunction "SER_14") (pintype "input"))
    )
    (net (code "150") (name "Net-(IC26-QH')") (class "Default")
      (node (ref "IC26") (pin "9") (pinfunction "QH'_9") (pintype "output"))
      (node (ref "R3") (pin "1") (pinfunction "1_1") (pintype "passive"))
    )
    (net (code "151") (name "P3V3A") (class "Default")
      (node (ref "C52") (pin "2") (pinfunction "2_2") (pintype "passive"))
      (node (ref "C53") (pin "2") (pinfunction "2_2") (pintype "passive"))
      (node (ref "C54") (pin "2") (pinfunction "2_2") (pintype "passive"))
      (node (ref "C55") (pin "2") (pinfunction "2_2") (pintype "passive"))
      (node (ref "C56") (pin "2") (pinfunction "2_2") (pintype "passive"))
      (node (ref "C57") (pin "2") (pinfunction "2_2") (pintype "passive"))
      (node (ref "C58") (pin "2") (pinfunction "2_2") (pintype "passive"))
      (node (ref "C59") (pin "2") (pinfunction "2_2") (pintype "passive"))
      (node (ref "C60") (pin "2") (pinfunction "2_2") (pintype "passive"))
      (node (ref "C61") (pin "2") (pinfunction "2_2") (pintype "passive"))
      (node (ref "C62") (pin "2") (pinfunction "2_2") (pintype "passive"))
      (node (ref "C63") (pin "2") (pinfunction "2_2") (pintype "passive"))
      (node (ref "C64") (pin "2") (pinfunction "2_2") (pintype "passive"))
      (node (ref "C65") (pin "2") (pinfunction "2_2") (pintype "passive"))
      (node (ref "C66") (pin "2") (pinfunction "2_2") (pintype "passive"))
      (node (ref "C67") (pin "2") (pinfunction "2_2") (pintype "passive"))
      (node (ref "C68") (pin "2") (pinfunction "2_2") (pintype "passive"))
      (node (ref "C69") (pin "2") (pinfunction "2_2") (pintype "passive"))
      (node (ref "IC12") (pin "10") (pinfunction "~{SRCLR}_10") (pintype "input"))
      (node (ref "IC12") (pin "16") (pinfunction "VCC_16") (pintype "power_in"))
      (node (ref "IC13") (pin "10") (pinfunction "~{SRCLR}_10") (pintype "input"))
      (node (ref "IC13") (pin "16") (pinfunction "VCC_16") (pintype "power_in"))
      (node (ref "IC14") (pin "10") (pinfunction "~{SRCLR}_10") (pintype "input"))
      (node (ref "IC14") (pin "16") (pinfunction "VCC_16") (pintype "power_in"))
      (node (ref "IC15") (pin "10") (pinfunction "~{SRCLR}_10") (pintype "input"))
      (node (ref "IC15") (pin "16") (pinfunction "VCC_16") (pintype "power_in"))
      (node (ref "IC16") (pin "10") (pinfunction "~{SRCLR}_10") (pintype "input"))
      (node (ref "IC16") (pin "16") (pinfunction "VCC_16") (pintype "power_in"))
      (node (ref "IC17") (pin "10") (pinfunction "~{SRCLR}_10") (pintype "input"))
      (node (ref "IC17") (pin "16") (pinfunction "VCC_16") (pintype "power_in"))
      (node (ref "IC18") (pin "10") (pinfunction "~{SRCLR}_10") (pintype "input"))
      (node (ref "IC18") (pin "16") (pinfunction "VCC_16") (pintype "power_in"))
      (node (ref "IC19") (pin "10") (pinfunction "~{SRCLR}_10") (pintype "input"))
      (node (ref "IC19") (pin "16") (pinfunction "VCC_16") (pintype "power_in"))
      (node (ref "IC20") (pin "10") (pinfunction "~{SRCLR}_10") (pintype "input"))
      (node (ref "IC20") (pin "16") (pinfunction "VCC_16") (pintype "power_in"))
      (node (ref "IC21") (pin "10") (pinfunction "~{SRCLR}_10") (pintype "input"))
      (node (ref "IC21") (pin "16") (pinfunction "VCC_16") (pintype "power_in"))
      (node (ref "IC22") (pin "10") (pinfunction "~{SRCLR}_10") (pintype "input"))
      (node (ref "IC22") (pin "16") (pinfunction "VCC_16") (pintype "power_in"))
      (node (ref "IC23") (pin "10") (pinfunction "~{SRCLR}_10") (pintype "input"))
      (node (ref "IC23") (pin "16") (pinfunction "VCC_16") (pintype "power_in"))
      (node (ref "IC24") (pin "10") (pinfunction "~{SRCLR}_10") (pintype "input"))
      (node (ref "IC24") (pin "16") (pinfunction "VCC_16") (pintype "power_in"))
      (node (ref "IC25") (pin "10") (pinfunction "~{SRCLR}_10") (pintype "input"))
      (node (ref "IC25") (pin "16") (pinfunction "VCC_16") (pintype "power_in"))
      (node (ref "IC26") (pin "10") (pinfunction "~{SRCLR}_10") (pintype "input"))
      (node (ref "IC26") (pin "16") (pinfunction "VCC_16") (pintype "power_in"))
      (node (ref "IC27") (pin "10") (pinfunction "~{SRCLR}_10") (pintype "input"))
      (node (ref "IC27") (pin "16") (pinfunction "VCC_16") (pintype "power_in"))
    )
  )
)
